# Z80.net
KiCad netlist of a schematic drawn in EAGLE
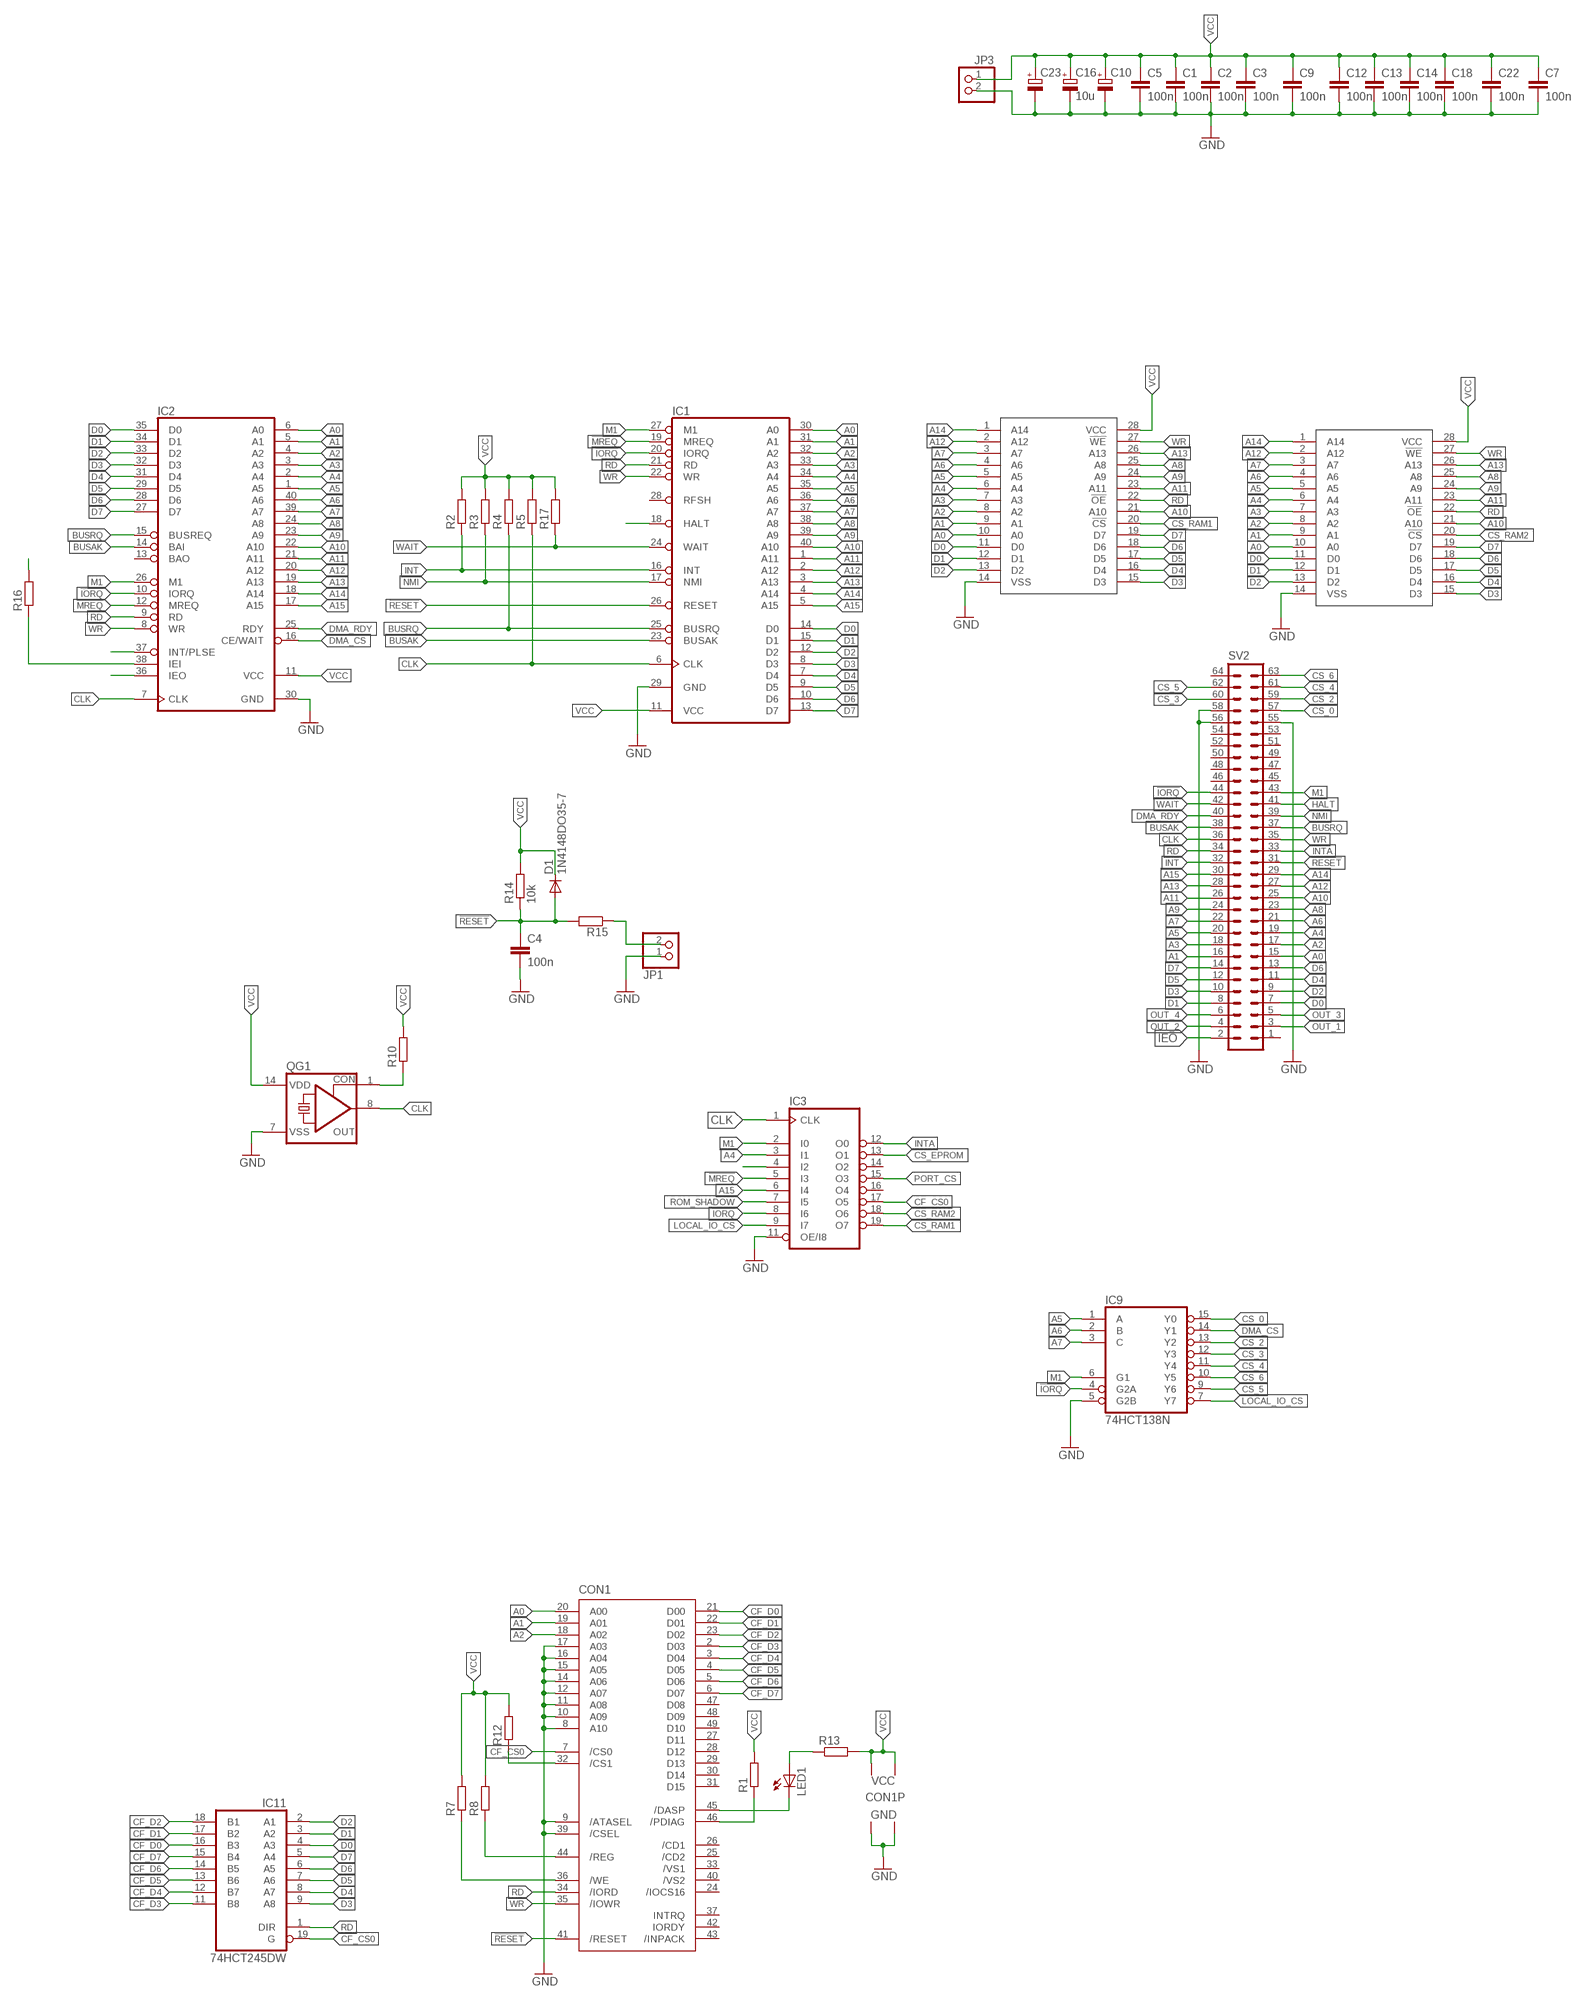
[diagram p0: schematic, sheet 1, part 1 of 2]
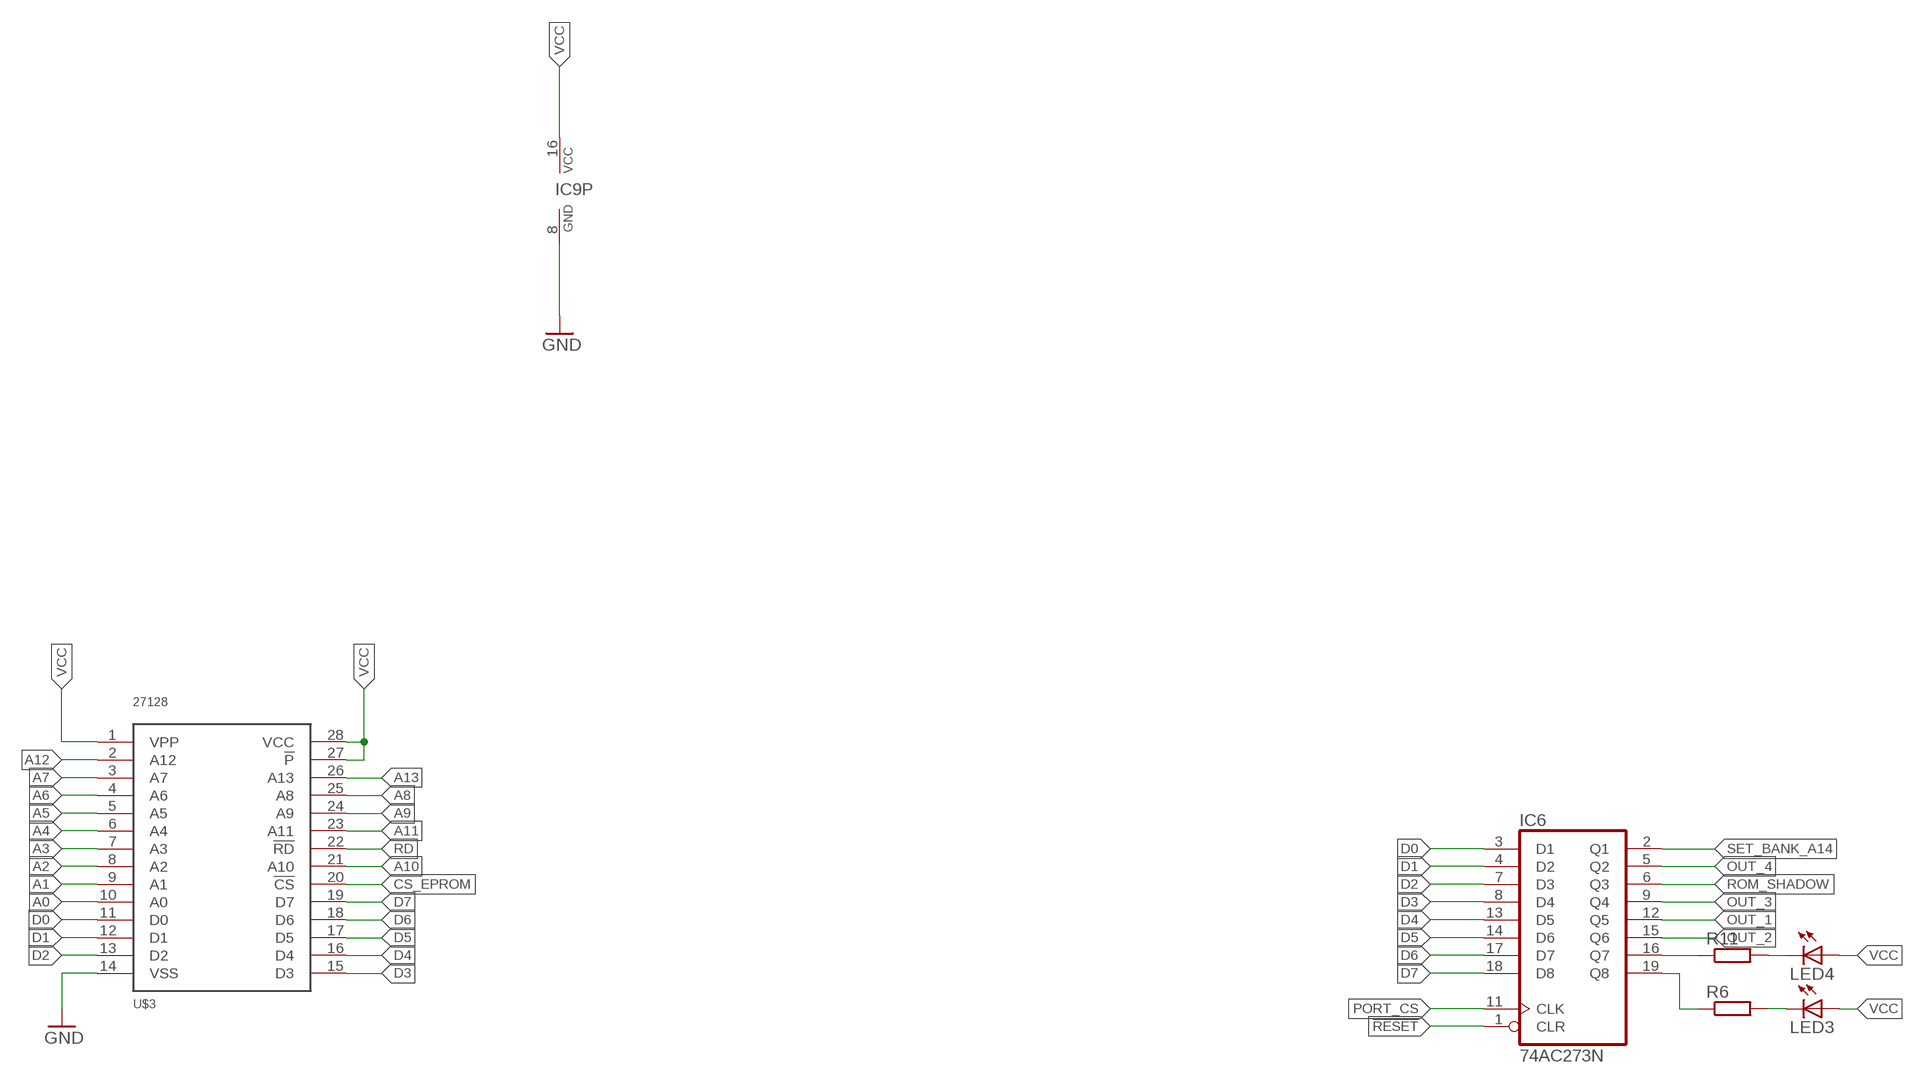
[diagram p1: schematic, sheet 1, part 2 of 2]

(export (version "E")
  (design (tool "Eeschema 10.0.6"))
  (components
    (comp (ref "C1")
      (value "100n")
      (footprint "eagle-import:C1206")
      (libsource (lib "eagle-import") (part "C-EUC1206"))
    )
    (comp (ref "C2")
      (value "100n")
      (footprint "eagle-import:C1206")
      (libsource (lib "eagle-import") (part "C-EUC1206"))
    )
    (comp (ref "C3")
      (value "100n")
      (footprint "eagle-import:C1206")
      (libsource (lib "eagle-import") (part "C-EUC1206"))
    )
    (comp (ref "C4")
      (value "100n")
      (footprint "eagle-import:C0603")
      (libsource (lib "eagle-import") (part "C-EUC0603"))
    )
    (comp (ref "C5")
      (value "100n")
      (footprint "eagle-import:C050-024X044")
      (libsource (lib "eagle-import") (part "C-EU050-024X044"))
    )
    (comp (ref "C7")
      (value "100n")
      (footprint "eagle-import:C0603")
      (libsource (lib "eagle-import") (part "C-EUC0603"))
    )
    (comp (ref "C9")
      (value "100n")
      (footprint "eagle-import:C1206")
      (libsource (lib "eagle-import") (part "C-EUC1206"))
    )
    (comp (ref "C10")
      (value "CPOL-EUE5-10.5")
      (footprint "eagle-import:E5-10,5")
      (libsource (lib "eagle-import") (part "CPOL-EUE5-10.5"))
    )
    (comp (ref "C12")
      (value "100n")
      (footprint "eagle-import:C0805")
      (libsource (lib "eagle-import") (part "C-EUC0805"))
    )
    (comp (ref "C13")
      (value "100n")
      (footprint "eagle-import:C0805")
      (libsource (lib "eagle-import") (part "C-EUC0805"))
    )
    (comp (ref "C14")
      (value "100n")
      (footprint "eagle-import:C1206")
      (libsource (lib "eagle-import") (part "C-EUC1206"))
    )
    (comp (ref "C16")
      (value "10u")
      (footprint "eagle-import:SMC_B")
      (libsource (lib "eagle-import") (part "CPOL-EUSMCB"))
    )
    (comp (ref "C18")
      (value "100n")
      (footprint "eagle-import:C0603")
      (libsource (lib "eagle-import") (part "C-EUC0603"))
    )
    (comp (ref "C22")
      (value "100n")
      (footprint "eagle-import:C0603")
      (libsource (lib "eagle-import") (part "C-EUC0603"))
    )
    (comp (ref "C23")
      (value "CPOL-EUE5-10.5")
      (footprint "eagle-import:E5-10,5")
      (libsource (lib "eagle-import") (part "CPOL-EUE5-10.5"))
    )
    (comp (ref "CON1")
      (value "CF-CARD-IDE_MODE")
      (footprint "eagle-import:MI20-50PD-SF")
      (libsource (lib "eagle-import") (part "CF-CARD-IDE_MODE"))
    )
    (comp (ref "D1")
      (value "1N4148DO35-7")
      (footprint "eagle-import:DO35-7")
      (libsource (lib "eagle-import") (part "1N4148DO35-7"))
    )
    (comp (ref "IC1")
      (value "Z80CPU")
      (footprint "eagle-import:DIL40")
      (libsource (lib "eagle-import") (part "Z80CPU"))
    )
    (comp (ref "IC2")
      (value "Z80DMA")
      (footprint "eagle-import:DIL40")
      (libsource (lib "eagle-import") (part "Z80DMA"))
    )
    (comp (ref "IC3")
      (value "16V8")
      (footprint "eagle-import:DIL20")
      (fields (field (name "MPN") "GAL16V8D-7LPN"))
      (libsource (lib "eagle-import") (part "16V8"))
    )
    (comp (ref "IC6")
      (value "74AC273N")
      (footprint "eagle-import:DIL20")
      (libsource (lib "eagle-import") (part "74273NAC"))
    )
    (comp (ref "IC9")
      (value "74HCT138N")
      (footprint "eagle-import:DIL16")
      (libsource (lib "eagle-import") (part "74138NHCT"))
    )
    (comp (ref "IC11")
      (value "74HCT245DW")
      (footprint "eagle-import:SO20W")
      (libsource (lib "eagle-import") (part "74245DWHCT"))
    )
    (comp (ref "JP1")
      (value "PINHD-1X2")
      (footprint "eagle-import:1X02")
      (libsource (lib "eagle-import") (part "PINHD-1X2"))
    )
    (comp (ref "JP3")
      (value "PINHD-1X2")
      (footprint "eagle-import:1X02")
      (libsource (lib "eagle-import") (part "PINHD-1X2"))
    )
    (comp (ref "LED1")
      (value "LED5MM")
      (footprint "eagle-import:LED5MM")
      (libsource (lib "eagle-import") (part "LED5MM"))
    )
    (comp (ref "LED3")
      (value "LED5MM")
      (footprint "eagle-import:LED5MM")
      (libsource (lib "eagle-import") (part "LED5MM"))
    )
    (comp (ref "LED4")
      (value "LED5MM")
      (footprint "eagle-import:LED5MM")
      (libsource (lib "eagle-import") (part "LED5MM"))
    )
    (comp (ref "QG1")
      (value "CRYSTAL_RES-SG51")
      (footprint "eagle-import:SG51")
      (libsource (lib "eagle-import") (part "CRYSTAL_RES-SG51"))
    )
    (comp (ref "R1")
      (value "R-EU_0204/7")
      (footprint "eagle-import:0204_7")
      (libsource (lib "eagle-import") (part "R-EU_0204/7"))
    )
    (comp (ref "R2")
      (value "R-EU_R1206")
      (footprint "eagle-import:R1206")
      (libsource (lib "eagle-import") (part "R-EU_R1206"))
    )
    (comp (ref "R3")
      (value "R-EU_R1206")
      (footprint "eagle-import:R1206")
      (libsource (lib "eagle-import") (part "R-EU_R1206"))
    )
    (comp (ref "R4")
      (value "R-EU_R0603")
      (footprint "eagle-import:R0603")
      (libsource (lib "eagle-import") (part "R-EU_R0603"))
    )
    (comp (ref "R5")
      (value "R-EU_R0603")
      (footprint "eagle-import:R0603")
      (libsource (lib "eagle-import") (part "R-EU_R0603"))
    )
    (comp (ref "R6")
      (value "R-EU_R1206")
      (footprint "eagle-import:R1206")
      (libsource (lib "eagle-import") (part "R-EU_R1206"))
    )
    (comp (ref "R7")
      (value "R-EU_0207/10")
      (footprint "eagle-import:0207_10")
      (libsource (lib "eagle-import") (part "R-EU_0207/10"))
    )
    (comp (ref "R8")
      (value "R-EU_0204/7")
      (footprint "eagle-import:0204_7")
      (libsource (lib "eagle-import") (part "R-EU_0204/7"))
    )
    (comp (ref "R10")
      (value "R-EU_R0603")
      (footprint "eagle-import:R0603")
      (libsource (lib "eagle-import") (part "R-EU_R0603"))
    )
    (comp (ref "R11")
      (value "R-EU_R1206")
      (footprint "eagle-import:R1206")
      (libsource (lib "eagle-import") (part "R-EU_R1206"))
    )
    (comp (ref "R12")
      (value "R-EU_0207/10")
      (footprint "eagle-import:0207_10")
      (libsource (lib "eagle-import") (part "R-EU_0207/10"))
    )
    (comp (ref "R13")
      (value "R-EU_R0603")
      (footprint "eagle-import:R0603")
      (libsource (lib "eagle-import") (part "R-EU_R0603"))
    )
    (comp (ref "R14")
      (value "10k")
      (footprint "eagle-import:0204_7")
      (libsource (lib "eagle-import") (part "R-EU_0204/7"))
    )
    (comp (ref "R15")
      (value "R-EU_R0603")
      (footprint "eagle-import:R0603")
      (libsource (lib "eagle-import") (part "R-EU_R0603"))
    )
    (comp (ref "R16")
      (value "R-EU_0204/5")
      (footprint "eagle-import:0204_5")
      (libsource (lib "eagle-import") (part "R-EU_0204/5"))
    )
    (comp (ref "R17")
      (value "R-EU_R0603")
      (footprint "eagle-import:R0603")
      (libsource (lib "eagle-import") (part "R-EU_R0603"))
    )
    (comp (ref "SV2")
      (value "ML64L")
      (footprint "eagle-import:ML64L")
      (libsource (lib "eagle-import") (part "ML64L"))
    )
    (comp (ref "U$2")
      (value "62256")
      (footprint "eagle-import:DIL28-6")
      (libsource (lib "eagle-import") (part "62256"))
    )
    (comp (ref "U$3")
      (value "27128")
      (footprint "eagle-import:DIL28")
      (libsource (lib "eagle-import") (part "27128"))
    )
    (comp (ref "U$4")
      (value "62256")
      (footprint "eagle-import:DIL28-6")
      (libsource (lib "eagle-import") (part "62256"))
    )
  )
  (nets
    (net (code "1") (name "/~{IORQ}") (class "Default")
      (node (ref "IC1") (pin "20") (pinfunction "IORQ_20") (pintype "output"))
      (node (ref "IC2") (pin "10") (pinfunction "IORQ_10") (pintype "bidirectional"))
      (node (ref "IC3") (pin "8") (pinfunction "I6_8") (pintype "input"))
      (node (ref "IC9") (pin "4") (pinfunction "G2A_4") (pintype "input"))
      (node (ref "SV2") (pin "44") (pinfunction "44_44") (pintype "passive"))
    )
    (net (code "2") (name "/~{MREQ}") (class "Default")
      (node (ref "IC1") (pin "19") (pinfunction "MREQ_19") (pintype "output"))
      (node (ref "IC2") (pin "12") (pinfunction "MREQ_12") (pintype "output"))
      (node (ref "IC3") (pin "5") (pinfunction "I3_5") (pintype "input"))
    )
    (net (code "3") (name "/~{RESET}") (class "Default")
      (node (ref "C4") (pin "1") (pinfunction "1_1") (pintype "passive"))
      (node (ref "CON1") (pin "41") (pinfunction "/RESET_41") (pintype "input"))
      (node (ref "D1") (pin "A") (pinfunction "A_A") (pintype "passive"))
      (node (ref "IC1") (pin "26") (pinfunction "RESET_26") (pintype "input"))
      (node (ref "IC6") (pin "1") (pinfunction "CLR_1") (pintype "input"))
      (node (ref "R14") (pin "1") (pinfunction "1_1") (pintype "passive"))
      (node (ref "R15") (pin "2") (pinfunction "2_2") (pintype "passive"))
      (node (ref "SV2") (pin "31") (pinfunction "31_31") (pintype "passive"))
    )
    (net (code "4") (name "A0") (class "Default")
      (node (ref "CON1") (pin "20") (pinfunction "A00_20") (pintype "input"))
      (node (ref "IC1") (pin "30") (pinfunction "A0_30") (pintype "output"))
      (node (ref "IC2") (pin "6") (pinfunction "A0_6") (pintype "output"))
      (node (ref "SV2") (pin "15") (pinfunction "15_15") (pintype "passive"))
      (node (ref "U$2") (pin "10") (pinfunction "A0_10") (pintype "bidirectional"))
      (node (ref "U$3") (pin "10") (pinfunction "A0_10") (pintype "bidirectional"))
      (node (ref "U$4") (pin "10") (pinfunction "A0_10") (pintype "bidirectional"))
    )
    (net (code "5") (name "A1") (class "Default")
      (node (ref "CON1") (pin "19") (pinfunction "A01_19") (pintype "input"))
      (node (ref "IC1") (pin "31") (pinfunction "A1_31") (pintype "output"))
      (node (ref "IC2") (pin "5") (pinfunction "A1_5") (pintype "output"))
      (node (ref "SV2") (pin "16") (pinfunction "16_16") (pintype "passive"))
      (node (ref "U$2") (pin "9") (pinfunction "A1_9") (pintype "bidirectional"))
      (node (ref "U$3") (pin "9") (pinfunction "A1_9") (pintype "bidirectional"))
      (node (ref "U$4") (pin "9") (pinfunction "A1_9") (pintype "bidirectional"))
    )
    (net (code "6") (name "A2") (class "Default")
      (node (ref "CON1") (pin "18") (pinfunction "A02_18") (pintype "input"))
      (node (ref "IC1") (pin "32") (pinfunction "A2_32") (pintype "output"))
      (node (ref "IC2") (pin "4") (pinfunction "A2_4") (pintype "output"))
      (node (ref "SV2") (pin "17") (pinfunction "17_17") (pintype "passive"))
      (node (ref "U$2") (pin "8") (pinfunction "A2_8") (pintype "bidirectional"))
      (node (ref "U$3") (pin "8") (pinfunction "A2_8") (pintype "bidirectional"))
      (node (ref "U$4") (pin "8") (pinfunction "A2_8") (pintype "bidirectional"))
    )
    (net (code "7") (name "A3") (class "Default")
      (node (ref "IC1") (pin "33") (pinfunction "A3_33") (pintype "output"))
      (node (ref "IC2") (pin "3") (pinfunction "A3_3") (pintype "output"))
      (node (ref "SV2") (pin "18") (pinfunction "18_18") (pintype "passive"))
      (node (ref "U$2") (pin "7") (pinfunction "A3_7") (pintype "bidirectional"))
      (node (ref "U$3") (pin "7") (pinfunction "A3_7") (pintype "bidirectional"))
      (node (ref "U$4") (pin "7") (pinfunction "A3_7") (pintype "bidirectional"))
    )
    (net (code "8") (name "A4") (class "Default")
      (node (ref "IC1") (pin "34") (pinfunction "A4_34") (pintype "output"))
      (node (ref "IC2") (pin "2") (pinfunction "A4_2") (pintype "output"))
      (node (ref "IC3") (pin "3") (pinfunction "I1_3") (pintype "input"))
      (node (ref "SV2") (pin "19") (pinfunction "19_19") (pintype "passive"))
      (node (ref "U$2") (pin "6") (pinfunction "A4_6") (pintype "bidirectional"))
      (node (ref "U$3") (pin "6") (pinfunction "A4_6") (pintype "bidirectional"))
      (node (ref "U$4") (pin "6") (pinfunction "A4_6") (pintype "bidirectional"))
    )
    (net (code "9") (name "A5") (class "Default")
      (node (ref "IC1") (pin "35") (pinfunction "A5_35") (pintype "output"))
      (node (ref "IC2") (pin "1") (pinfunction "A5_1") (pintype "output"))
      (node (ref "IC9") (pin "1") (pinfunction "A_1") (pintype "input"))
      (node (ref "SV2") (pin "20") (pinfunction "20_20") (pintype "passive"))
      (node (ref "U$2") (pin "5") (pinfunction "A5_5") (pintype "bidirectional"))
      (node (ref "U$3") (pin "5") (pinfunction "A5_5") (pintype "bidirectional"))
      (node (ref "U$4") (pin "5") (pinfunction "A5_5") (pintype "bidirectional"))
    )
    (net (code "10") (name "A6") (class "Default")
      (node (ref "IC1") (pin "36") (pinfunction "A6_36") (pintype "output"))
      (node (ref "IC2") (pin "40") (pinfunction "A6_40") (pintype "output"))
      (node (ref "IC9") (pin "2") (pinfunction "B_2") (pintype "input"))
      (node (ref "SV2") (pin "21") (pinfunction "21_21") (pintype "passive"))
      (node (ref "U$2") (pin "4") (pinfunction "A6_4") (pintype "bidirectional"))
      (node (ref "U$3") (pin "4") (pinfunction "A6_4") (pintype "bidirectional"))
      (node (ref "U$4") (pin "4") (pinfunction "A6_4") (pintype "bidirectional"))
    )
    (net (code "11") (name "A7") (class "Default")
      (node (ref "IC1") (pin "37") (pinfunction "A7_37") (pintype "output"))
      (node (ref "IC2") (pin "39") (pinfunction "A7_39") (pintype "output"))
      (node (ref "IC9") (pin "3") (pinfunction "C_3") (pintype "input"))
      (node (ref "SV2") (pin "22") (pinfunction "22_22") (pintype "passive"))
      (node (ref "U$2") (pin "3") (pinfunction "A7_3") (pintype "bidirectional"))
      (node (ref "U$3") (pin "3") (pinfunction "A7_3") (pintype "bidirectional"))
      (node (ref "U$4") (pin "3") (pinfunction "A7_3") (pintype "bidirectional"))
    )
    (net (code "12") (name "A8") (class "Default")
      (node (ref "IC1") (pin "38") (pinfunction "A8_38") (pintype "output"))
      (node (ref "IC2") (pin "24") (pinfunction "A8_24") (pintype "output"))
      (node (ref "SV2") (pin "23") (pinfunction "23_23") (pintype "passive"))
      (node (ref "U$2") (pin "25") (pinfunction "A8_25") (pintype "bidirectional"))
      (node (ref "U$3") (pin "25") (pinfunction "A8_25") (pintype "bidirectional"))
      (node (ref "U$4") (pin "25") (pinfunction "A8_25") (pintype "bidirectional"))
    )
    (net (code "13") (name "A9") (class "Default")
      (node (ref "IC1") (pin "39") (pinfunction "A9_39") (pintype "output"))
      (node (ref "IC2") (pin "23") (pinfunction "A9_23") (pintype "output"))
      (node (ref "SV2") (pin "24") (pinfunction "24_24") (pintype "passive"))
      (node (ref "U$2") (pin "24") (pinfunction "A9_24") (pintype "bidirectional"))
      (node (ref "U$3") (pin "24") (pinfunction "A9_24") (pintype "bidirectional"))
      (node (ref "U$4") (pin "24") (pinfunction "A9_24") (pintype "bidirectional"))
    )
    (net (code "14") (name "A10") (class "Default")
      (node (ref "IC1") (pin "40") (pinfunction "A10_40") (pintype "output"))
      (node (ref "IC2") (pin "22") (pinfunction "A10_22") (pintype "output"))
      (node (ref "SV2") (pin "25") (pinfunction "25_25") (pintype "passive"))
      (node (ref "U$2") (pin "21") (pinfunction "A10_21") (pintype "bidirectional"))
      (node (ref "U$3") (pin "21") (pinfunction "A10_21") (pintype "bidirectional"))
      (node (ref "U$4") (pin "21") (pinfunction "A10_21") (pintype "bidirectional"))
    )
    (net (code "15") (name "A11") (class "Default")
      (node (ref "IC1") (pin "1") (pinfunction "A11_1") (pintype "output"))
      (node (ref "IC2") (pin "21") (pinfunction "A11_21") (pintype "output"))
      (node (ref "SV2") (pin "26") (pinfunction "26_26") (pintype "passive"))
      (node (ref "U$2") (pin "23") (pinfunction "A11_23") (pintype "bidirectional"))
      (node (ref "U$3") (pin "23") (pinfunction "A11_23") (pintype "bidirectional"))
      (node (ref "U$4") (pin "23") (pinfunction "A11_23") (pintype "bidirectional"))
    )
    (net (code "16") (name "A12") (class "Default")
      (node (ref "IC1") (pin "2") (pinfunction "A12_2") (pintype "output"))
      (node (ref "IC2") (pin "20") (pinfunction "A12_20") (pintype "output"))
      (node (ref "SV2") (pin "27") (pinfunction "27_27") (pintype "passive"))
      (node (ref "U$2") (pin "2") (pinfunction "A12_2") (pintype "bidirectional"))
      (node (ref "U$3") (pin "2") (pinfunction "A12_2") (pintype "bidirectional"))
      (node (ref "U$4") (pin "2") (pinfunction "A12_2") (pintype "bidirectional"))
    )
    (net (code "17") (name "A13") (class "Default")
      (node (ref "IC1") (pin "3") (pinfunction "A13_3") (pintype "output"))
      (node (ref "IC2") (pin "19") (pinfunction "A13_19") (pintype "output"))
      (node (ref "SV2") (pin "28") (pinfunction "28_28") (pintype "passive"))
      (node (ref "U$2") (pin "26") (pinfunction "A13_26") (pintype "bidirectional"))
      (node (ref "U$3") (pin "26") (pinfunction "A13_26") (pintype "bidirectional"))
      (node (ref "U$4") (pin "26") (pinfunction "A13_26") (pintype "bidirectional"))
    )
    (net (code "18") (name "A14") (class "Default")
      (node (ref "IC1") (pin "4") (pinfunction "A14_4") (pintype "output"))
      (node (ref "IC2") (pin "18") (pinfunction "A14_18") (pintype "output"))
      (node (ref "SV2") (pin "29") (pinfunction "29_29") (pintype "passive"))
      (node (ref "U$2") (pin "1") (pinfunction "A14_1") (pintype "bidirectional"))
      (node (ref "U$4") (pin "1") (pinfunction "A14_1") (pintype "bidirectional"))
    )
    (net (code "19") (name "A15") (class "Default")
      (node (ref "IC1") (pin "5") (pinfunction "A15_5") (pintype "output"))
      (node (ref "IC2") (pin "17") (pinfunction "A15_17") (pintype "output"))
      (node (ref "IC3") (pin "6") (pinfunction "I4_6") (pintype "input"))
      (node (ref "SV2") (pin "30") (pinfunction "30_30") (pintype "passive"))
    )
    (net (code "20") (name "BUSAK") (class "Default")
      (node (ref "IC1") (pin "23") (pinfunction "BUSAK_23") (pintype "output"))
      (node (ref "IC2") (pin "14") (pinfunction "BAI_14") (pintype "input"))
      (node (ref "SV2") (pin "38") (pinfunction "38_38") (pintype "passive"))
    )
    (net (code "21") (name "BUSRQ") (class "Default")
      (node (ref "IC1") (pin "25") (pinfunction "BUSRQ_25") (pintype "input"))
      (node (ref "IC2") (pin "15") (pinfunction "BUSREQ_15") (pintype "bidirectional"))
      (node (ref "R4") (pin "1") (pinfunction "1_1") (pintype "passive"))
      (node (ref "SV2") (pin "37") (pinfunction "37_37") (pintype "passive"))
    )
    (net (code "22") (name "CF_CS0") (class "Default")
      (node (ref "CON1") (pin "7") (pinfunction "/CS0_7") (pintype "input"))
      (node (ref "IC11") (pin "19") (pinfunction "G_19") (pintype "input"))
      (node (ref "IC3") (pin "17") (pinfunction "O5_17") (pintype "bidirectional"))
    )
    (net (code "23") (name "CF_D0") (class "Default")
      (node (ref "CON1") (pin "21") (pinfunction "D00_21") (pintype "bidirectional"))
      (node (ref "IC11") (pin "16") (pinfunction "B3_16") (pintype "bidirectional"))
    )
    (net (code "24") (name "CF_D1") (class "Default")
      (node (ref "CON1") (pin "22") (pinfunction "D01_22") (pintype "bidirectional"))
      (node (ref "IC11") (pin "17") (pinfunction "B2_17") (pintype "bidirectional"))
    )
    (net (code "25") (name "CF_D2") (class "Default")
      (node (ref "CON1") (pin "23") (pinfunction "D02_23") (pintype "bidirectional"))
      (node (ref "IC11") (pin "18") (pinfunction "B1_18") (pintype "bidirectional"))
    )
    (net (code "26") (name "CF_D3") (class "Default")
      (node (ref "CON1") (pin "2") (pinfunction "D03_2") (pintype "bidirectional"))
      (node (ref "IC11") (pin "11") (pinfunction "B8_11") (pintype "bidirectional"))
    )
    (net (code "27") (name "CF_D4") (class "Default")
      (node (ref "CON1") (pin "3") (pinfunction "D04_3") (pintype "bidirectional"))
      (node (ref "IC11") (pin "12") (pinfunction "B7_12") (pintype "bidirectional"))
    )
    (net (code "28") (name "CF_D5") (class "Default")
      (node (ref "CON1") (pin "4") (pinfunction "D05_4") (pintype "bidirectional"))
      (node (ref "IC11") (pin "13") (pinfunction "B6_13") (pintype "bidirectional"))
    )
    (net (code "29") (name "CF_D6") (class "Default")
      (node (ref "CON1") (pin "5") (pinfunction "D06_5") (pintype "bidirectional"))
      (node (ref "IC11") (pin "14") (pinfunction "B5_14") (pintype "bidirectional"))
    )
    (net (code "30") (name "CF_D7") (class "Default")
      (node (ref "CON1") (pin "6") (pinfunction "D07_6") (pintype "bidirectional"))
      (node (ref "IC11") (pin "15") (pinfunction "B4_15") (pintype "bidirectional"))
    )
    (net (code "31") (name "CLK") (class "Default")
      (node (ref "IC1") (pin "6") (pinfunction "CLK_6") (pintype "input"))
      (node (ref "IC2") (pin "7") (pinfunction "CLK_7") (pintype "input"))
      (node (ref "IC3") (pin "1") (pinfunction "CLK_1") (pintype "input"))
      (node (ref "QG1") (pin "8") (pinfunction "OUT_8") (pintype "output"))
      (node (ref "R5") (pin "1") (pinfunction "1_1") (pintype "passive"))
      (node (ref "SV2") (pin "36") (pinfunction "36_36") (pintype "passive"))
    )
    (net (code "32") (name "CS_0") (class "Default")
      (node (ref "IC9") (pin "15") (pinfunction "Y0_15") (pintype "output"))
      (node (ref "SV2") (pin "57") (pinfunction "57_57") (pintype "passive"))
    )
    (net (code "33") (name "CS_2") (class "Default")
      (node (ref "IC9") (pin "13") (pinfunction "Y2_13") (pintype "output"))
      (node (ref "SV2") (pin "59") (pinfunction "59_59") (pintype "passive"))
    )
    (net (code "34") (name "CS_3") (class "Default")
      (node (ref "IC9") (pin "12") (pinfunction "Y3_12") (pintype "output"))
      (node (ref "SV2") (pin "60") (pinfunction "60_60") (pintype "passive"))
    )
    (net (code "35") (name "CS_4") (class "Default")
      (node (ref "IC9") (pin "11") (pinfunction "Y4_11") (pintype "output"))
      (node (ref "SV2") (pin "61") (pinfunction "61_61") (pintype "passive"))
    )
    (net (code "36") (name "CS_5") (class "Default")
      (node (ref "IC9") (pin "9") (pinfunction "Y6_9") (pintype "output"))
      (node (ref "SV2") (pin "62") (pinfunction "62_62") (pintype "passive"))
    )
    (net (code "37") (name "CS_6") (class "Default")
      (node (ref "IC9") (pin "10") (pinfunction "Y5_10") (pintype "output"))
      (node (ref "SV2") (pin "63") (pinfunction "63_63") (pintype "passive"))
    )
    (net (code "38") (name "CS_EPROM") (class "Default")
      (node (ref "IC3") (pin "13") (pinfunction "O1_13") (pintype "bidirectional"))
      (node (ref "U$3") (pin "20") (pinfunction "~{CS}_20") (pintype "bidirectional"))
    )
    (net (code "39") (name "CS_RAM1") (class "Default")
      (node (ref "IC3") (pin "19") (pinfunction "O7_19") (pintype "bidirectional"))
      (node (ref "U$4") (pin "20") (pinfunction "~{CS}_20") (pintype "bidirectional"))
    )
    (net (code "40") (name "CS_RAM2") (class "Default")
      (node (ref "IC3") (pin "18") (pinfunction "O6_18") (pintype "bidirectional"))
      (node (ref "U$2") (pin "20") (pinfunction "~{CS}_20") (pintype "bidirectional"))
    )
    (net (code "41") (name "D0") (class "Default")
      (node (ref "IC1") (pin "14") (pinfunction "D0_14") (pintype "bidirectional"))
      (node (ref "IC11") (pin "4") (pinfunction "A3_4") (pintype "bidirectional"))
      (node (ref "IC2") (pin "35") (pinfunction "D0_35") (pintype "bidirectional"))
      (node (ref "IC6") (pin "3") (pinfunction "D1_3") (pintype "input"))
      (node (ref "SV2") (pin "7") (pinfunction "7_7") (pintype "passive"))
      (node (ref "U$2") (pin "11") (pinfunction "D0_11") (pintype "bidirectional"))
      (node (ref "U$3") (pin "11") (pinfunction "D0_11") (pintype "bidirectional"))
      (node (ref "U$4") (pin "11") (pinfunction "D0_11") (pintype "bidirectional"))
    )
    (net (code "42") (name "D1") (class "Default")
      (node (ref "IC1") (pin "15") (pinfunction "D1_15") (pintype "bidirectional"))
      (node (ref "IC11") (pin "3") (pinfunction "A2_3") (pintype "bidirectional"))
      (node (ref "IC2") (pin "34") (pinfunction "D1_34") (pintype "bidirectional"))
      (node (ref "IC6") (pin "4") (pinfunction "D2_4") (pintype "input"))
      (node (ref "SV2") (pin "8") (pinfunction "8_8") (pintype "passive"))
      (node (ref "U$2") (pin "12") (pinfunction "D1_12") (pintype "bidirectional"))
      (node (ref "U$3") (pin "12") (pinfunction "D1_12") (pintype "bidirectional"))
      (node (ref "U$4") (pin "12") (pinfunction "D1_12") (pintype "bidirectional"))
    )
    (net (code "43") (name "D2") (class "Default")
      (node (ref "IC1") (pin "12") (pinfunction "D2_12") (pintype "bidirectional"))
      (node (ref "IC11") (pin "2") (pinfunction "A1_2") (pintype "bidirectional"))
      (node (ref "IC2") (pin "33") (pinfunction "D2_33") (pintype "bidirectional"))
      (node (ref "IC6") (pin "7") (pinfunction "D3_7") (pintype "input"))
      (node (ref "SV2") (pin "9") (pinfunction "9_9") (pintype "passive"))
      (node (ref "U$2") (pin "13") (pinfunction "D2_13") (pintype "bidirectional"))
      (node (ref "U$3") (pin "13") (pinfunction "D2_13") (pintype "bidirectional"))
      (node (ref "U$4") (pin "13") (pinfunction "D2_13") (pintype "bidirectional"))
    )
    (net (code "44") (name "D3") (class "Default")
      (node (ref "IC1") (pin "8") (pinfunction "D3_8") (pintype "bidirectional"))
      (node (ref "IC11") (pin "9") (pinfunction "A8_9") (pintype "bidirectional"))
      (node (ref "IC2") (pin "32") (pinfunction "D3_32") (pintype "bidirectional"))
      (node (ref "IC6") (pin "8") (pinfunction "D4_8") (pintype "input"))
      (node (ref "SV2") (pin "10") (pinfunction "10_10") (pintype "passive"))
      (node (ref "U$2") (pin "15") (pinfunction "D3_15") (pintype "bidirectional"))
      (node (ref "U$3") (pin "15") (pinfunction "D3_15") (pintype "bidirectional"))
      (node (ref "U$4") (pin "15") (pinfunction "D3_15") (pintype "bidirectional"))
    )
    (net (code "45") (name "D4") (class "Default")
      (node (ref "IC1") (pin "7") (pinfunction "D4_7") (pintype "bidirectional"))
      (node (ref "IC11") (pin "8") (pinfunction "A7_8") (pintype "bidirectional"))
      (node (ref "IC2") (pin "31") (pinfunction "D4_31") (pintype "bidirectional"))
      (node (ref "IC6") (pin "13") (pinfunction "D5_13") (pintype "input"))
      (node (ref "SV2") (pin "11") (pinfunction "11_11") (pintype "passive"))
      (node (ref "U$2") (pin "16") (pinfunction "D4_16") (pintype "bidirectional"))
      (node (ref "U$3") (pin "16") (pinfunction "D4_16") (pintype "bidirectional"))
      (node (ref "U$4") (pin "16") (pinfunction "D4_16") (pintype "bidirectional"))
    )
    (net (code "46") (name "D5") (class "Default")
      (node (ref "IC1") (pin "9") (pinfunction "D5_9") (pintype "bidirectional"))
      (node (ref "IC11") (pin "7") (pinfunction "A6_7") (pintype "bidirectional"))
      (node (ref "IC2") (pin "29") (pinfunction "D5_29") (pintype "bidirectional"))
      (node (ref "IC6") (pin "14") (pinfunction "D6_14") (pintype "input"))
      (node (ref "SV2") (pin "12") (pinfunction "12_12") (pintype "passive"))
      (node (ref "U$2") (pin "17") (pinfunction "D5_17") (pintype "bidirectional"))
      (node (ref "U$3") (pin "17") (pinfunction "D5_17") (pintype "bidirectional"))
      (node (ref "U$4") (pin "17") (pinfunction "D5_17") (pintype "bidirectional"))
    )
    (net (code "47") (name "D6") (class "Default")
      (node (ref "IC1") (pin "10") (pinfunction "D6_10") (pintype "bidirectional"))
      (node (ref "IC11") (pin "6") (pinfunction "A5_6") (pintype "bidirectional"))
      (node (ref "IC2") (pin "28") (pinfunction "D6_28") (pintype "bidirectional"))
      (node (ref "IC6") (pin "17") (pinfunction "D7_17") (pintype "input"))
      (node (ref "SV2") (pin "13") (pinfunction "13_13") (pintype "passive"))
      (node (ref "U$2") (pin "18") (pinfunction "D6_18") (pintype "bidirectional"))
      (node (ref "U$3") (pin "18") (pinfunction "D6_18") (pintype "bidirectional"))
      (node (ref "U$4") (pin "18") (pinfunction "D6_18") (pintype "bidirectional"))
    )
    (net (code "48") (name "D7") (class "Default")
      (node (ref "IC1") (pin "13") (pinfunction "D7_13") (pintype "bidirectional"))
      (node (ref "IC11") (pin "5") (pinfunction "A4_5") (pintype "bidirectional"))
      (node (ref "IC2") (pin "27") (pinfunction "D7_27") (pintype "bidirectional"))
      (node (ref "IC6") (pin "18") (pinfunction "D8_18") (pintype "input"))
      (node (ref "SV2") (pin "14") (pinfunction "14_14") (pintype "passive"))
      (node (ref "U$2") (pin "19") (pinfunction "D7_19") (pintype "bidirectional"))
      (node (ref "U$3") (pin "19") (pinfunction "D7_19") (pintype "bidirectional"))
      (node (ref "U$4") (pin "19") (pinfunction "D7_19") (pintype "bidirectional"))
    )
    (net (code "49") (name "DMA_CS") (class "Default")
      (node (ref "IC2") (pin "16") (pinfunction "CE/WAIT_16") (pintype "input"))
      (node (ref "IC9") (pin "14") (pinfunction "Y1_14") (pintype "output"))
    )
    (net (code "50") (name "DMA_RDY") (class "Default")
      (node (ref "IC2") (pin "25") (pinfunction "RDY_25") (pintype "input"))
      (node (ref "SV2") (pin "40") (pinfunction "40_40") (pintype "passive"))
    )
    (net (code "51") (name "GND") (class "Default")
      (node (ref "C1") (pin "2") (pinfunction "2_2") (pintype "passive"))
      (node (ref "C10") (pin "-") (pinfunction "-_-") (pintype "passive"))
      (node (ref "C12") (pin "2") (pinfunction "2_2") (pintype "passive"))
      (node (ref "C13") (pin "2") (pinfunction "2_2") (pintype "passive"))
      (node (ref "C14") (pin "2") (pinfunction "2_2") (pintype "passive"))
      (node (ref "C16") (pin "-") (pinfunction "-_-") (pintype "passive"))
      (node (ref "C18") (pin "2") (pinfunction "2_2") (pintype "passive"))
      (node (ref "C2") (pin "2") (pinfunction "2_2") (pintype "passive"))
      (node (ref "C22") (pin "2") (pinfunction "2_2") (pintype "passive"))
      (node (ref "C23") (pin "-") (pinfunction "-_-") (pintype "passive"))
      (node (ref "C3") (pin "2") (pinfunction "2_2") (pintype "passive"))
      (node (ref "C4") (pin "2") (pinfunction "2_2") (pintype "passive"))
      (node (ref "C5") (pin "2") (pinfunction "2_2") (pintype "passive"))
      (node (ref "C7") (pin "2") (pinfunction "2_2") (pintype "passive"))
      (node (ref "C9") (pin "2") (pinfunction "2_2") (pintype "passive"))
      (node (ref "CON1") (pin "1") (pinfunction "GND1_1") (pintype "power_in"))
      (node (ref "CON1") (pin "10") (pinfunction "A09_10") (pintype "input"))
      (node (ref "CON1") (pin "11") (pinfunction "A08_11") (pintype "input"))
      (node (ref "CON1") (pin "12") (pinfunction "A07_12") (pintype "input"))
      (node (ref "CON1") (pin "14") (pinfunction "A06_14") (pintype "input"))
      (node (ref "CON1") (pin "15") (pinfunction "A05_15") (pintype "input"))
      (node (ref "CON1") (pin "16") (pinfunction "A04_16") (pintype "input"))
      (node (ref "CON1") (pin "17") (pinfunction "A03_17") (pintype "input"))
      (node (ref "CON1") (pin "39") (pinfunction "/CSEL_39") (pintype "input"))
      (node (ref "CON1") (pin "50") (pinfunction "GND2_50") (pintype "power_in"))
      (node (ref "CON1") (pin "8") (pinfunction "A10_8") (pintype "input"))
      (node (ref "CON1") (pin "9") (pinfunction "/ATASEL_9") (pintype "input"))
      (node (ref "IC1") (pin "29") (pinfunction "GND_29") (pintype "power_in"))
      (node (ref "IC2") (pin "30") (pinfunction "GND_30") (pintype "power_in"))
      (node (ref "IC3") (pin "11") (pinfunction "OE/I8_11") (pintype "input"))
      (node (ref "IC9") (pin "5") (pinfunction "G2B_5") (pintype "input"))
      (node (ref "IC9") (pin "8") (pinfunction "GND_8") (pintype "power_in"))
      (node (ref "JP1") (pin "1") (pinfunction "1_1") (pintype "passive"))
      (node (ref "JP3") (pin "2") (pinfunction "2_2") (pintype "passive"))
      (node (ref "QG1") (pin "7") (pinfunction "VSS_7") (pintype "power_in"))
      (node (ref "SV2") (pin "55") (pinfunction "55_55") (pintype "passive"))
      (node (ref "SV2") (pin "56") (pinfunction "56_56") (pintype "passive"))
      (node (ref "SV2") (pin "58") (pinfunction "58_58") (pintype "passive"))
      (node (ref "U$2") (pin "14") (pinfunction "VSS_14") (pintype "bidirectional"))
      (node (ref "U$3") (pin "14") (pinfunction "VSS_14") (pintype "bidirectional"))
      (node (ref "U$4") (pin "14") (pinfunction "VSS_14") (pintype "bidirectional"))
    )
    (net (code "52") (name "HALT") (class "Default")
      (node (ref "IC1") (pin "18") (pinfunction "HALT_18") (pintype "output"))
      (node (ref "SV2") (pin "41") (pinfunction "41_41") (pintype "passive"))
    )
    (net (code "53") (name "IEO") (class "Default")
      (node (ref "IC2") (pin "36") (pinfunction "IEO_36") (pintype "output"))
      (node (ref "SV2") (pin "2") (pinfunction "2_2") (pintype "passive"))
    )
    (net (code "54") (name "INT") (class "Default")
      (node (ref "IC1") (pin "16") (pinfunction "INT_16") (pintype "input"))
      (node (ref "IC2") (pin "37") (pinfunction "INT/PLSE_37") (pintype "open_collector"))
      (node (ref "R2") (pin "1") (pinfunction "1_1") (pintype "passive"))
      (node (ref "SV2") (pin "32") (pinfunction "32_32") (pintype "passive"))
    )
    (net (code "55") (name "INTA") (class "Default")
      (node (ref "IC3") (pin "12") (pinfunction "O0_12") (pintype "bidirectional"))
      (node (ref "SV2") (pin "33") (pinfunction "33_33") (pintype "passive"))
    )
    (net (code "56") (name "LOCAL_IO_CS") (class "Default")
      (node (ref "IC3") (pin "9") (pinfunction "I7_9") (pintype "input"))
      (node (ref "IC9") (pin "7") (pinfunction "Y7_7") (pintype "output"))
    )
    (net (code "57") (name "M1") (class "Default")
      (node (ref "IC1") (pin "27") (pinfunction "M1_27") (pintype "output"))
      (node (ref "IC2") (pin "26") (pinfunction "M1_26") (pintype "input"))
      (node (ref "IC3") (pin "2") (pinfunction "I0_2") (pintype "input"))
      (node (ref "IC9") (pin "6") (pinfunction "G1_6") (pintype "input"))
      (node (ref "SV2") (pin "43") (pinfunction "43_43") (pintype "passive"))
    )
    (net (code "58") (name "NMI") (class "Default")
      (node (ref "IC1") (pin "17") (pinfunction "NMI_17") (pintype "input"))
      (node (ref "R3") (pin "1") (pinfunction "1_1") (pintype "passive"))
      (node (ref "SV2") (pin "39") (pinfunction "39_39") (pintype "passive"))
    )
    (net (code "59") (name "Net-(CON1A-{slash}CS1)") (class "Default")
      (node (ref "CON1") (pin "32") (pinfunction "/CS1_32") (pintype "input"))
      (node (ref "R12") (pin "1") (pinfunction "1_1") (pintype "passive"))
    )
    (net (code "60") (name "Net-(CON1A-{slash}DASP)") (class "Default")
      (node (ref "CON1") (pin "45") (pinfunction "/DASP_45") (pintype "bidirectional"))
      (node (ref "LED1") (pin "K") (pinfunction "C_K") (pintype "passive"))
    )
    (net (code "61") (name "Net-(CON1A-{slash}PDIAG)") (class "Default")
      (node (ref "CON1") (pin "46") (pinfunction "/PDIAG_46") (pintype "bidirectional"))
      (node (ref "R1") (pin "1") (pinfunction "1_1") (pintype "passive"))
    )
    (net (code "62") (name "Net-(CON1A-{slash}REG)") (class "Default")
      (node (ref "CON1") (pin "44") (pinfunction "/REG_44") (pintype "input"))
      (node (ref "R8") (pin "1") (pinfunction "1_1") (pintype "passive"))
    )
    (net (code "63") (name "Net-(CON1A-{slash}WE)") (class "Default")
      (node (ref "CON1") (pin "36") (pinfunction "/WE_36") (pintype "input"))
      (node (ref "R7") (pin "1") (pinfunction "1_1") (pintype "passive"))
    )
    (net (code "64") (name "Net-(IC2-IEI)") (class "Default")
      (node (ref "IC2") (pin "38") (pinfunction "IEI_38") (pintype "input"))
      (node (ref "R16") (pin "1") (pinfunction "1_1") (pintype "passive"))
    )
    (net (code "65") (name "Net-(IC6A-Q7)") (class "Default")
      (node (ref "IC6") (pin "16") (pinfunction "Q7_16") (pintype "output"))
      (node (ref "R11") (pin "1") (pinfunction "1_1") (pintype "passive"))
    )
    (net (code "66") (name "Net-(IC6A-Q8)") (class "Default")
      (node (ref "IC6") (pin "19") (pinfunction "Q8_19") (pintype "output"))
      (node (ref "R6") (pin "1") (pinfunction "1_1") (pintype "passive"))
    )
    (net (code "67") (name "Net-(JP1-Pad2)") (class "Default")
      (node (ref "JP1") (pin "2") (pinfunction "2_2") (pintype "passive"))
      (node (ref "R15") (pin "1") (pinfunction "1_1") (pintype "passive"))
    )
    (net (code "68") (name "Net-(LED1-PadA)") (class "Default")
      (node (ref "LED1") (pin "A") (pinfunction "A_A") (pintype "passive"))
      (node (ref "R13") (pin "1") (pinfunction "1_1") (pintype "passive"))
    )
    (net (code "69") (name "Net-(LED3-C)") (class "Default")
      (node (ref "LED3") (pin "K") (pinfunction "C_K") (pintype "passive"))
      (node (ref "R6") (pin "2") (pinfunction "2_2") (pintype "passive"))
    )
    (net (code "70") (name "Net-(LED4-C)") (class "Default")
      (node (ref "LED4") (pin "K") (pinfunction "C_K") (pintype "passive"))
      (node (ref "R11") (pin "2") (pinfunction "2_2") (pintype "passive"))
    )
    (net (code "71") (name "Net-(QG1-CON)") (class "Default")
      (node (ref "QG1") (pin "1") (pinfunction "CON_1") (pintype "input"))
      (node (ref "R10") (pin "1") (pinfunction "1_1") (pintype "passive"))
    )
    (net (code "72") (name "OUT_1") (class "Default")
      (node (ref "IC6") (pin "12") (pinfunction "Q5_12") (pintype "output"))
      (node (ref "SV2") (pin "3") (pinfunction "3_3") (pintype "passive"))
    )
    (net (code "73") (name "OUT_2") (class "Default")
      (node (ref "IC6") (pin "15") (pinfunction "Q6_15") (pintype "output"))
      (node (ref "SV2") (pin "4") (pinfunction "4_4") (pintype "passive"))
    )
    (net (code "74") (name "OUT_3") (class "Default")
      (node (ref "IC6") (pin "9") (pinfunction "Q4_9") (pintype "output"))
      (node (ref "SV2") (pin "5") (pinfunction "5_5") (pintype "passive"))
    )
    (net (code "75") (name "OUT_4") (class "Default")
      (node (ref "IC6") (pin "5") (pinfunction "Q2_5") (pintype "output"))
      (node (ref "SV2") (pin "6") (pinfunction "6_6") (pintype "passive"))
    )
    (net (code "76") (name "PORT_CS") (class "Default")
      (node (ref "IC3") (pin "15") (pinfunction "O3_15") (pintype "bidirectional"))
      (node (ref "IC6") (pin "11") (pinfunction "CLK_11") (pintype "input"))
    )
    (net (code "77") (name "RD") (class "Default")
      (node (ref "CON1") (pin "34") (pinfunction "/IORD_34") (pintype "input"))
      (node (ref "IC1") (pin "21") (pinfunction "RD_21") (pintype "output"))
      (node (ref "IC11") (pin "1") (pinfunction "DIR_1") (pintype "input"))
      (node (ref "IC2") (pin "9") (pinfunction "RD_9") (pintype "bidirectional"))
      (node (ref "SV2") (pin "34") (pinfunction "34_34") (pintype "passive"))
      (node (ref "U$2") (pin "22") (pinfunction "~{OE}_22") (pintype "bidirectional"))
      (node (ref "U$3") (pin "22") (pinfunction "~{RD}_22") (pintype "bidirectional"))
      (node (ref "U$4") (pin "22") (pinfunction "~{OE}_22") (pintype "bidirectional"))
    )
    (net (code "78") (name "ROM_SHADOW") (class "Default")
      (node (ref "IC3") (pin "7") (pinfunction "I5_7") (pintype "input"))
      (node (ref "IC6") (pin "6") (pinfunction "Q3_6") (pintype "output"))
    )
    (net (code "79") (name "SET_BANK_A14") (class "Default")
      (node (ref "IC6") (pin "2") (pinfunction "Q1_2") (pintype "output"))
    )
    (net (code "80") (name "VCC") (class "Default")
      (node (ref "C1") (pin "1") (pinfunction "1_1") (pintype "passive"))
      (node (ref "C10") (pin "+") (pinfunction "+_+") (pintype "passive"))
      (node (ref "C12") (pin "1") (pinfunction "1_1") (pintype "passive"))
      (node (ref "C13") (pin "1") (pinfunction "1_1") (pintype "passive"))
      (node (ref "C14") (pin "1") (pinfunction "1_1") (pintype "passive"))
      (node (ref "C16") (pin "+") (pinfunction "+_+") (pintype "passive"))
      (node (ref "C18") (pin "1") (pinfunction "1_1") (pintype "passive"))
      (node (ref "C2") (pin "1") (pinfunction "1_1") (pintype "passive"))
      (node (ref "C22") (pin "1") (pinfunction "1_1") (pintype "passive"))
      (node (ref "C23") (pin "+") (pinfunction "+_+") (pintype "passive"))
      (node (ref "C3") (pin "1") (pinfunction "1_1") (pintype "passive"))
      (node (ref "C5") (pin "1") (pinfunction "1_1") (pintype "passive"))
      (node (ref "C7") (pin "1") (pinfunction "1_1") (pintype "passive"))
      (node (ref "C9") (pin "1") (pinfunction "1_1") (pintype "passive"))
      (node (ref "CON1") (pin "13") (pinfunction "VCC2_13") (pintype "power_in"))
      (node (ref "CON1") (pin "38") (pinfunction "VCC1_38") (pintype "power_in"))
      (node (ref "D1") (pin "C") (pinfunction "C_C") (pintype "passive"))
      (node (ref "IC1") (pin "11") (pinfunction "VCC_11") (pintype "power_in"))
      (node (ref "IC2") (pin "11") (pinfunction "VCC_11") (pintype "power_in"))
      (node (ref "IC9") (pin "16") (pinfunction "VCC_16") (pintype "power_in"))
      (node (ref "JP3") (pin "1") (pinfunction "1_1") (pintype "passive"))
      (node (ref "LED3") (pin "A") (pinfunction "A_A") (pintype "passive"))
      (node (ref "LED4") (pin "A") (pinfunction "A_A") (pintype "passive"))
      (node (ref "QG1") (pin "14") (pinfunction "VDD_14") (pintype "power_in"))
      (node (ref "R1") (pin "2") (pinfunction "2_2") (pintype "passive"))
      (node (ref "R10") (pin "2") (pinfunction "2_2") (pintype "passive"))
      (node (ref "R12") (pin "2") (pinfunction "2_2") (pintype "passive"))
      (node (ref "R13") (pin "2") (pinfunction "2_2") (pintype "passive"))
      (node (ref "R14") (pin "2") (pinfunction "2_2") (pintype "passive"))
      (node (ref "R16") (pin "2") (pinfunction "2_2") (pintype "passive"))
      (node (ref "R17") (pin "2") (pinfunction "2_2") (pintype "passive"))
      (node (ref "R2") (pin "2") (pinfunction "2_2") (pintype "passive"))
      (node (ref "R3") (pin "2") (pinfunction "2_2") (pintype "passive"))
      (node (ref "R4") (pin "2") (pinfunction "2_2") (pintype "passive"))
      (node (ref "R5") (pin "2") (pinfunction "2_2") (pintype "passive"))
      (node (ref "R7") (pin "2") (pinfunction "2_2") (pintype "passive"))
      (node (ref "R8") (pin "2") (pinfunction "2_2") (pintype "passive"))
      (node (ref "U$2") (pin "28") (pinfunction "VCC_28") (pintype "bidirectional"))
      (node (ref "U$3") (pin "1") (pinfunction "VPP_1") (pintype "bidirectional"))
      (node (ref "U$3") (pin "27") (pinfunction "~{P}_27") (pintype "bidirectional"))
      (node (ref "U$3") (pin "28") (pinfunction "VCC_28") (pintype "bidirectional"))
      (node (ref "U$4") (pin "28") (pinfunction "VCC_28") (pintype "bidirectional"))
    )
    (net (code "81") (name "WAIT") (class "Default")
      (node (ref "IC1") (pin "24") (pinfunction "WAIT_24") (pintype "input"))
      (node (ref "R17") (pin "1") (pinfunction "1_1") (pintype "passive"))
      (node (ref "SV2") (pin "42") (pinfunction "42_42") (pintype "passive"))
    )
    (net (code "82") (name "WR") (class "Default")
      (node (ref "CON1") (pin "35") (pinfunction "/IOWR_35") (pintype "input"))
      (node (ref "IC1") (pin "22") (pinfunction "WR_22") (pintype "output"))
      (node (ref "IC2") (pin "8") (pinfunction "WR_8") (pintype "bidirectional"))
      (node (ref "IC3") (pin "4") (pinfunction "I2_4") (pintype "input"))
      (node (ref "SV2") (pin "35") (pinfunction "35_35") (pintype "passive"))
      (node (ref "U$2") (pin "27") (pinfunction "~{WE}_27") (pintype "bidirectional"))
      (node (ref "U$4") (pin "27") (pinfunction "~{WE}_27") (pintype "bidirectional"))
    )
    (net (code "83") (name "unconnected-(CON1A-D08-Pad47)") (class "Default")
      (node (ref "CON1") (pin "47") (pinfunction "D08_47") (pintype "bidirectional"))
    )
    (net (code "84") (name "unconnected-(CON1A-D09-Pad48)") (class "Default")
      (node (ref "CON1") (pin "48") (pinfunction "D09_48") (pintype "bidirectional"))
    )
    (net (code "85") (name "unconnected-(CON1A-D10-Pad49)") (class "Default")
      (node (ref "CON1") (pin "49") (pinfunction "D10_49") (pintype "bidirectional"))
    )
    (net (code "86") (name "unconnected-(CON1A-D11-Pad27)") (class "Default")
      (node (ref "CON1") (pin "27") (pinfunction "D11_27") (pintype "bidirectional"))
    )
    (net (code "87") (name "unconnected-(CON1A-D12-Pad28)") (class "Default")
      (node (ref "CON1") (pin "28") (pinfunction "D12_28") (pintype "bidirectional"))
    )
    (net (code "88") (name "unconnected-(CON1A-D13-Pad29)") (class "Default")
      (node (ref "CON1") (pin "29") (pinfunction "D13_29") (pintype "bidirectional"))
    )
    (net (code "89") (name "unconnected-(CON1A-D14-Pad30)") (class "Default")
      (node (ref "CON1") (pin "30") (pinfunction "D14_30") (pintype "bidirectional"))
    )
    (net (code "90") (name "unconnected-(CON1A-D15-Pad31)") (class "Default")
      (node (ref "CON1") (pin "31") (pinfunction "D15_31") (pintype "bidirectional"))
    )
    (net (code "91") (name "unconnected-(CON1A-INTRQ-Pad37)") (class "Default")
      (node (ref "CON1") (pin "37") (pinfunction "INTRQ_37") (pintype "output"))
    )
    (net (code "92") (name "unconnected-(CON1A-IORDY-Pad42)") (class "Default")
      (node (ref "CON1") (pin "42") (pinfunction "IORDY_42") (pintype "output"))
    )
    (net (code "93") (name "unconnected-(CON1A-{slash}CD1-Pad26)") (class "Default")
      (node (ref "CON1") (pin "26") (pinfunction "/CD1_26") (pintype "output"))
    )
    (net (code "94") (name "unconnected-(CON1A-{slash}CD2-Pad25)") (class "Default")
      (node (ref "CON1") (pin "25") (pinfunction "/CD2_25") (pintype "output"))
    )
    (net (code "95") (name "unconnected-(CON1A-{slash}INPACK-Pad43)") (class "Default")
      (node (ref "CON1") (pin "43") (pinfunction "/INPACK_43") (pintype "output"))
    )
    (net (code "96") (name "unconnected-(CON1A-{slash}IOCS16-Pad24)") (class "Default")
      (node (ref "CON1") (pin "24") (pinfunction "/IOCS16_24") (pintype "output"))
    )
    (net (code "97") (name "unconnected-(CON1A-{slash}VS1-Pad33)") (class "Default")
      (node (ref "CON1") (pin "33") (pinfunction "/VS1_33") (pintype "output"))
    )
    (net (code "98") (name "unconnected-(CON1A-{slash}VS2-Pad40)") (class "Default")
      (node (ref "CON1") (pin "40") (pinfunction "/VS2_40") (pintype "output"))
    )
    (net (code "99") (name "unconnected-(IC1-RFSH-Pad28)") (class "Default")
      (node (ref "IC1") (pin "28") (pinfunction "RFSH_28") (pintype "output"))
    )
    (net (code "100") (name "unconnected-(IC2-BAO-Pad13)") (class "Default")
      (node (ref "IC2") (pin "13") (pinfunction "BAO_13") (pintype "output"))
    )
    (net (code "101") (name "unconnected-(IC3A-O2-Pad14)") (class "Default")
      (node (ref "IC3") (pin "14") (pinfunction "O2_14") (pintype "bidirectional"))
    )
    (net (code "102") (name "unconnected-(IC3A-O4-Pad16)") (class "Default")
      (node (ref "IC3") (pin "16") (pinfunction "O4_16") (pintype "bidirectional"))
    )
    (net (code "103") (name "unconnected-(SV2-Pad1)") (class "Default")
      (node (ref "SV2") (pin "1") (pinfunction "1_1") (pintype "passive"))
    )
    (net (code "104") (name "unconnected-(SV2-Pad45)") (class "Default")
      (node (ref "SV2") (pin "45") (pinfunction "45_45") (pintype "passive"))
    )
    (net (code "105") (name "unconnected-(SV2-Pad46)") (class "Default")
      (node (ref "SV2") (pin "46") (pinfunction "46_46") (pintype "passive"))
    )
    (net (code "106") (name "unconnected-(SV2-Pad47)") (class "Default")
      (node (ref "SV2") (pin "47") (pinfunction "47_47") (pintype "passive"))
    )
    (net (code "107") (name "unconnected-(SV2-Pad48)") (class "Default")
      (node (ref "SV2") (pin "48") (pinfunction "48_48") (pintype "passive"))
    )
    (net (code "108") (name "unconnected-(SV2-Pad49)") (class "Default")
      (node (ref "SV2") (pin "49") (pinfunction "49_49") (pintype "passive"))
    )
    (net (code "109") (name "unconnected-(SV2-Pad50)") (class "Default")
      (node (ref "SV2") (pin "50") (pinfunction "50_50") (pintype "passive"))
    )
    (net (code "110") (name "unconnected-(SV2-Pad51)") (class "Default")
      (node (ref "SV2") (pin "51") (pinfunction "51_51") (pintype "passive"))
    )
    (net (code "111") (name "unconnected-(SV2-Pad52)") (class "Default")
      (node (ref "SV2") (pin "52") (pinfunction "52_52") (pintype "passive"))
    )
    (net (code "112") (name "unconnected-(SV2-Pad53)") (class "Default")
      (node (ref "SV2") (pin "53") (pinfunction "53_53") (pintype "passive"))
    )
    (net (code "113") (name "unconnected-(SV2-Pad54)") (class "Default")
      (node (ref "SV2") (pin "54") (pinfunction "54_54") (pintype "passive"))
    )
    (net (code "114") (name "unconnected-(SV2-Pad64)") (class "Default")
      (node (ref "SV2") (pin "64") (pinfunction "64_64") (pintype "passive"))
    )
  )
)
